# DMXRX.net
KiCad netlist of a schematic drawn in EAGLE
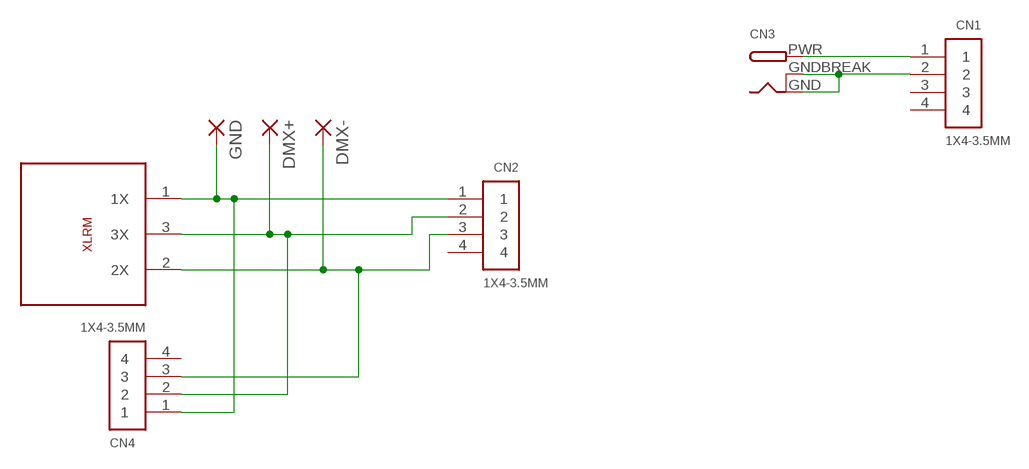
[diagram p0: schematic, sheet 1]

(export (version "E")
  (design (tool "Eeschema 10.0.6"))
  (components
    (comp (ref "CN1")
      (value "1X4-3.5MM")
      (footprint "eagle-import:1X04-3.5MM")
      (libsource (lib "eagle-import") (part "1X4-3.5MM"))
    )
    (comp (ref "CN2")
      (value "1X4-3.5MM")
      (footprint "eagle-import:1X04-3.5MM")
      (libsource (lib "eagle-import") (part "1X4-3.5MM"))
    )
    (comp (ref "CN3")
      (value "DCBARRELPTH")
      (footprint "eagle-import:DCJACK_2MM_PTH")
      (libsource (lib "eagle-import") (part "DCBARRELPTH"))
    )
    (comp (ref "CN4")
      (value "1X4-3.5MM")
      (footprint "eagle-import:1X04-3.5MM")
      (libsource (lib "eagle-import") (part "1X4-3.5MM"))
    )
    (comp (ref "DMX+")
      (value "3,81/1,4")
      (footprint "eagle-import:3,81_1,4")
      (libsource (lib "eagle-import") (part "3,81/1,4"))
    )
    (comp (ref "DMX-")
      (value "3,81/1,4")
      (footprint "eagle-import:3,81_1,4")
      (libsource (lib "eagle-import") (part "3,81/1,4"))
    )
    (comp (ref "GND")
      (value "3,81/1,4")
      (footprint "eagle-import:3,81_1,4")
      (libsource (lib "eagle-import") (part "3,81/1,4"))
    )
    (comp (ref "U$1")
      (value "XLRCONNCTORM")
      (footprint "eagle-import:DMX3PINF")
      (libsource (lib "eagle-import") (part "XLRCONNCTORM"))
    )
  )
  (nets
    (net (code "1") (name "Net-(CN1-Pad1)") (class "Default")
      (node (ref "CN1") (pin "1") (pinfunction "1_1") (pintype "bidirectional"))
      (node (ref "CN3") (pin "PWR") (pinfunction "PWR_PWR") (pintype "power_in"))
    )
    (net (code "2") (name "Net-(CN1-Pad2)") (class "Default")
      (node (ref "CN1") (pin "2") (pinfunction "2_2") (pintype "bidirectional"))
      (node (ref "CN3") (pin "GND") (pinfunction "GND_GND") (pintype "power_in"))
      (node (ref "CN3") (pin "GNDBREAK") (pinfunction "GNDBREAK_GNDBREAK") (pintype "power_in"))
    )
    (net (code "3") (name "Net-(DMX+-P)") (class "Default")
      (node (ref "CN2") (pin "2") (pinfunction "2_2") (pintype "bidirectional"))
      (node (ref "CN4") (pin "2") (pinfunction "2_2") (pintype "bidirectional"))
      (node (ref "DMX+") (pin "1") (pinfunction "P_1") (pintype "passive"))
      (node (ref "U$1") (pin "3") (pinfunction "3X_3") (pintype "bidirectional"))
    )
    (net (code "4") (name "Net-(DMX--P)") (class "Default")
      (node (ref "CN2") (pin "3") (pinfunction "3_3") (pintype "bidirectional"))
      (node (ref "CN4") (pin "3") (pinfunction "3_3") (pintype "bidirectional"))
      (node (ref "DMX-") (pin "1") (pinfunction "P_1") (pintype "passive"))
      (node (ref "U$1") (pin "2") (pinfunction "2X_2") (pintype "bidirectional"))
    )
    (net (code "5") (name "Net-(GND-P)") (class "Default")
      (node (ref "CN2") (pin "1") (pinfunction "1_1") (pintype "bidirectional"))
      (node (ref "CN4") (pin "1") (pinfunction "1_1") (pintype "bidirectional"))
      (node (ref "GND") (pin "1") (pinfunction "P_1") (pintype "passive"))
      (node (ref "U$1") (pin "1") (pinfunction "1X_1") (pintype "bidirectional"))
    )
    (net (code "6") (name "unconnected-(CN1-Pad3)") (class "Default")
      (node (ref "CN1") (pin "3") (pinfunction "3_3") (pintype "bidirectional"))
    )
    (net (code "7") (name "unconnected-(CN1-Pad4)") (class "Default")
      (node (ref "CN1") (pin "4") (pinfunction "4_4") (pintype "bidirectional"))
    )
    (net (code "8") (name "unconnected-(CN2-Pad4)") (class "Default")
      (node (ref "CN2") (pin "4") (pinfunction "4_4") (pintype "bidirectional"))
    )
    (net (code "9") (name "unconnected-(CN4-Pad4)") (class "Default")
      (node (ref "CN4") (pin "4") (pinfunction "4_4") (pintype "bidirectional"))
    )
  )
)
